# FMC_connector.net
KiCad netlist of a schematic drawn in Altium Designer
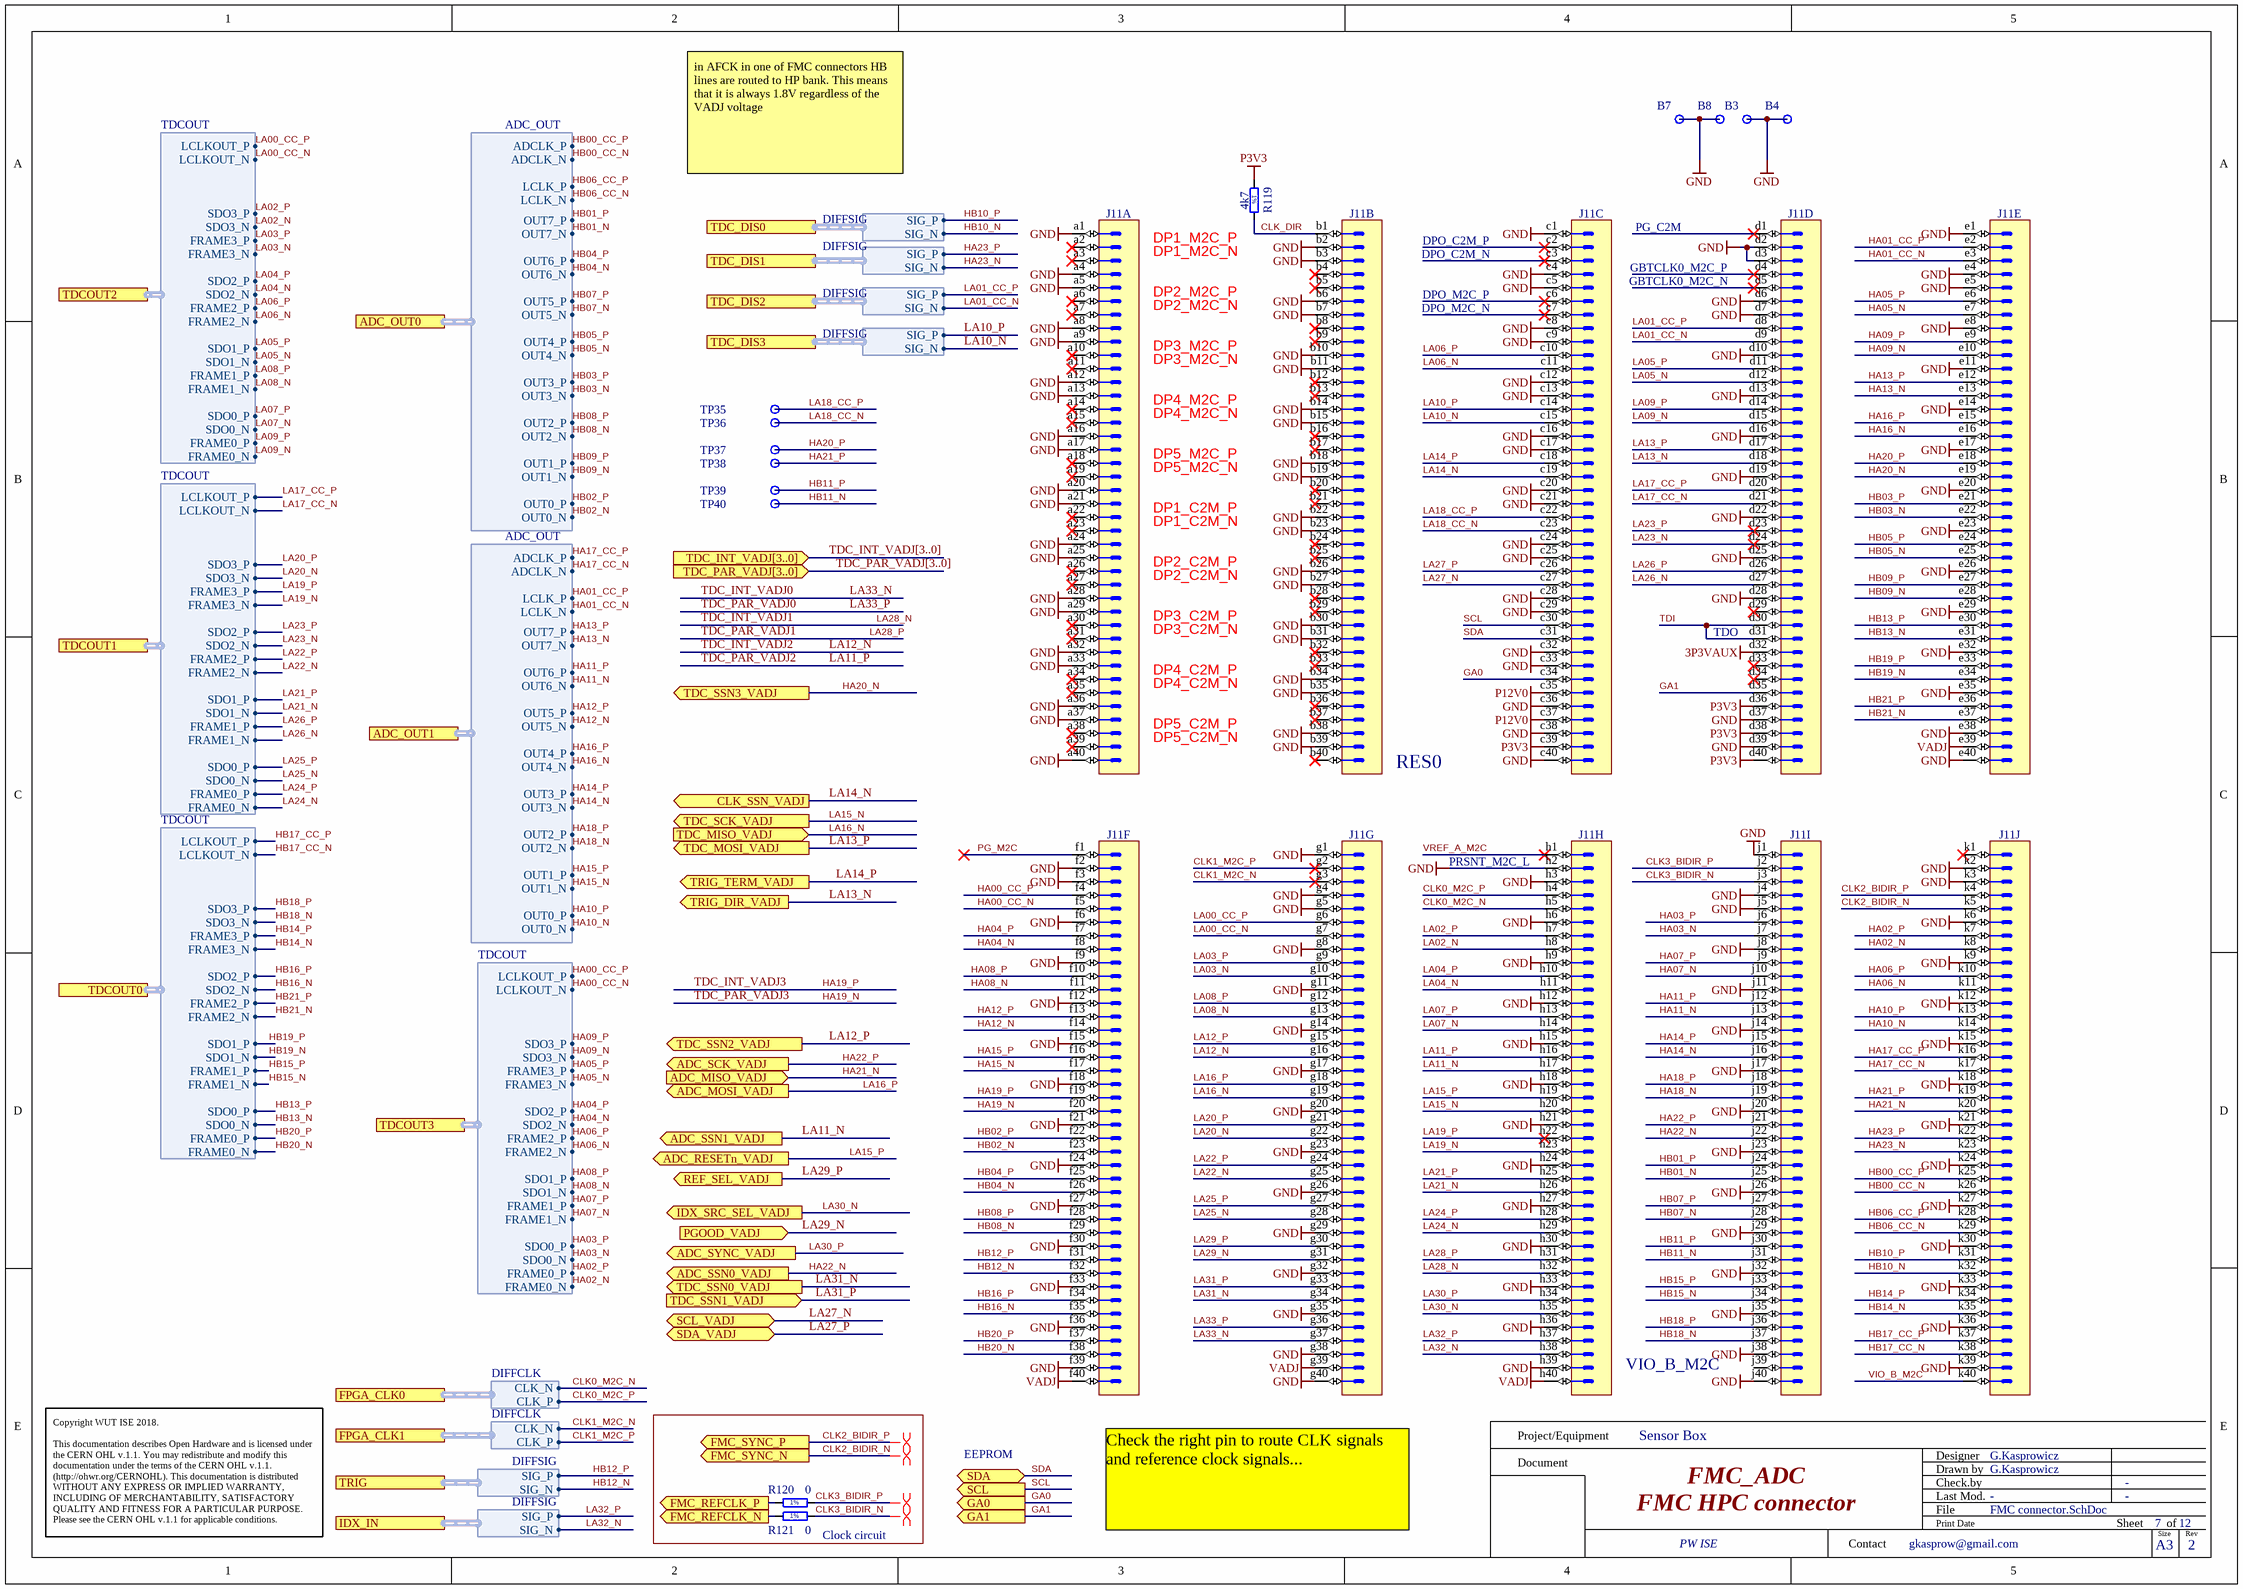
[diagram p0: FMC connector.SchDoc]

(export (version "E")
  (design (tool "Eeschema 10.0.6"))
  (components
    (comp (ref "B3")
      (value "Plated Hole")
      (footprint "MTG300_600")
      (description "Single Terminal Socket")
      (fields (field (name "PART NUMBER") "PLATED_HOLE3.0_PAD6.0") (field (name "AUTHOR") "CERN DEM JLC"))
      (libsource (lib "Eletro-mechanical") (part "Single Terminal Socket"))
    )
    (comp (ref "B4")
      (value "Plated Hole")
      (footprint "MTG300_600")
      (description "Single Terminal Socket")
      (fields (field (name "PART NUMBER") "PLATED_HOLE3.0_PAD6.0") (field (name "AUTHOR") "CERN DEM JLC"))
      (libsource (lib "Eletro-mechanical") (part "Single Terminal Socket"))
    )
    (comp (ref "B7")
      (value "Plated Hole")
      (footprint "MTG300_600")
      (description "Single Terminal Socket")
      (fields (field (name "PART NUMBER") "PLATED_HOLE3.0_PAD6.0") (field (name "AUTHOR") "CERN DEM JLC"))
      (libsource (lib "Eletro-mechanical") (part "Single Terminal Socket"))
    )
    (comp (ref "B8")
      (value "Plated Hole")
      (footprint "MTG300_600")
      (description "Single Terminal Socket")
      (fields (field (name "PART NUMBER") "PLATED_HOLE3.0_PAD6.0") (field (name "AUTHOR") "CERN DEM JLC"))
      (libsource (lib "Eletro-mechanical") (part "Single Terminal Socket"))
    )
    (comp (ref "J11")
      (value "VITA 57")
      (footprint "SAMTEC_ASP-134488-01")
      (description "Connector VITA 57, 400 Male contacts in 10 row abcdefghj")
      (fields
        (field (name "PART NUMBER") "SAMTEC_ASP-134488-01")
        (field (name "MANUFACTURER") "SAMTEC")
        (field (name "AUTHOR") "CERN DEM JLC")
      )
      (libsource (lib "Connectors") (part "Connector VITA 57 400 Male (abcdefghjk)"))
    )
    (comp (ref "R119")
      (value "4k7")
      (footprint "RESC1608X55N")
      (description "Resistor - 1%")
      (fields
        (field (name "PART NUMBER") "R0603_4K7_1%_0.1W_100PPM")
        (field (name "POWER") "0.1W")
        (field (name "AUTHOR") "CERN DEM JLC")
      )
      (libsource (lib "Resistors") (part "Resistor - 1%"))
    )
    (comp (ref "R120")
      (value "0")
      (footprint "RESC1005X40N")
      (description "Resistor - 1%")
      (fields
        (field (name "PART NUMBER") "R0402_0R_JUMPER")
        (field (name "MANUFACTURER") "GENERIC")
        (field (name "AUTHOR") "CERN DEM JLC")
      )
      (libsource (lib "Resistors") (part "Resistor - 1%"))
    )
    (comp (ref "R121")
      (value "0")
      (footprint "RESC1005X40N")
      (description "Resistor - 1%")
      (fields
        (field (name "PART NUMBER") "R0402_0R_JUMPER")
        (field (name "MANUFACTURER") "GENERIC")
        (field (name "AUTHOR") "CERN DEM JLC")
      )
      (libsource (lib "Resistors") (part "Resistor - 1%"))
    )
    (comp (ref "TP35")
      (value "Test Point")
      (footprint "TPS127")
      (fields (field (name "PART NUMBER") "SMD_PAD_1.27X1.27MM") (field (name "AUTHOR") "CERN DEM JLC"))
      (libsource (lib "Eletro-mechanical") (part "Test Point"))
    )
    (comp (ref "TP36")
      (value "Test Point")
      (footprint "TPS127")
      (fields (field (name "PART NUMBER") "SMD_PAD_1.27X1.27MM") (field (name "AUTHOR") "CERN DEM JLC"))
      (libsource (lib "Eletro-mechanical") (part "Test Point"))
    )
    (comp (ref "TP37")
      (value "Test Point")
      (footprint "TPS127")
      (fields (field (name "PART NUMBER") "SMD_PAD_1.27X1.27MM") (field (name "AUTHOR") "CERN DEM JLC"))
      (libsource (lib "Eletro-mechanical") (part "Test Point"))
    )
    (comp (ref "TP38")
      (value "Test Point")
      (footprint "TPS127")
      (fields (field (name "PART NUMBER") "SMD_PAD_1.27X1.27MM") (field (name "AUTHOR") "CERN DEM JLC"))
      (libsource (lib "Eletro-mechanical") (part "Test Point"))
    )
    (comp (ref "TP39")
      (value "Test Point")
      (footprint "TPS127")
      (fields (field (name "PART NUMBER") "SMD_PAD_1.27X1.27MM") (field (name "AUTHOR") "CERN DEM JLC"))
      (libsource (lib "Eletro-mechanical") (part "Test Point"))
    )
    (comp (ref "TP40")
      (value "Test Point")
      (footprint "TPS127")
      (fields (field (name "PART NUMBER") "SMD_PAD_1.27X1.27MM") (field (name "AUTHOR") "CERN DEM JLC"))
      (libsource (lib "Eletro-mechanical") (part "Test Point"))
    )
  )
  (nets
    (net (code "5") (name "/CLK0_M2C_N") (class "Default")
      (node (ref "J11") (pin "h5") (pinfunction "h5_h5") (pintype "bidirectional"))
    )
    (net (code "6") (name "/CLK0_M2C_P") (class "Default")
      (node (ref "J11") (pin "h4") (pinfunction "h4_h4") (pintype "bidirectional"))
    )
    (net (code "7") (name "/CLK1_M2C_N") (class "Default")
      (node (ref "J11") (pin "g3") (pinfunction "g3_g3") (pintype "bidirectional"))
    )
    (net (code "8") (name "/CLK1_M2C_P") (class "Default")
      (node (ref "J11") (pin "g2") (pinfunction "g2_g2") (pintype "bidirectional"))
    )
    (net (code "9") (name "/CLK2_BIDIR_N") (class "Default")
      (node (ref "J11") (pin "k5") (pinfunction "k5_k5") (pintype "bidirectional"))
    )
    (net (code "10") (name "/CLK2_BIDIR_P") (class "Default")
      (node (ref "J11") (pin "k4") (pinfunction "k4_k4") (pintype "bidirectional"))
    )
    (net (code "11") (name "/CLK3_BIDIR_N") (class "Default")
      (node (ref "J11") (pin "j3") (pinfunction "j3_j3") (pintype "bidirectional"))
      (node (ref "R121") (pin "2") (pinfunction "2_2") (pintype "passive"))
    )
    (net (code "12") (name "/CLK3_BIDIR_P") (class "Default")
      (node (ref "J11") (pin "j2") (pinfunction "j2_j2") (pintype "bidirectional"))
      (node (ref "R120") (pin "2") (pinfunction "2_2") (pintype "passive"))
    )
    (net (code "13") (name "/CLK_DIR") (class "Default")
      (node (ref "J11") (pin "b1") (pinfunction "b1_b1") (pintype "bidirectional"))
      (node (ref "R119") (pin "2") (pinfunction "2_2") (pintype "passive"))
    )
    (net (code "14") (name "/FMC_REFCLK_N") (class "Default")
      (node (ref "R121") (pin "1") (pinfunction "1_1") (pintype "passive"))
    )
    (net (code "15") (name "/FMC_REFCLK_P") (class "Default")
      (node (ref "R120") (pin "1") (pinfunction "1_1") (pintype "passive"))
    )
    (net (code "16") (name "/GA0") (class "Default")
      (node (ref "J11") (pin "c34") (pinfunction "c34_c34") (pintype "bidirectional"))
    )
    (net (code "17") (name "/GA1") (class "Default")
      (node (ref "J11") (pin "d35") (pinfunction "d35_d35") (pintype "bidirectional"))
    )
    (net (code "18") (name "/HA00_CC_N") (class "Default")
      (node (ref "J11") (pin "f5") (pinfunction "f5_f5") (pintype "bidirectional"))
    )
    (net (code "19") (name "/HA00_CC_P") (class "Default")
      (node (ref "J11") (pin "f4") (pinfunction "f4_f4") (pintype "bidirectional"))
    )
    (net (code "20") (name "/HA01_CC_N") (class "Default")
      (node (ref "J11") (pin "e3") (pinfunction "e3_e3") (pintype "bidirectional"))
    )
    (net (code "21") (name "/HA01_CC_P") (class "Default")
      (node (ref "J11") (pin "e2") (pinfunction "e2_e2") (pintype "bidirectional"))
    )
    (net (code "22") (name "/HA02_N") (class "Default")
      (node (ref "J11") (pin "k8") (pinfunction "k8_k8") (pintype "bidirectional"))
    )
    (net (code "23") (name "/HA02_P") (class "Default")
      (node (ref "J11") (pin "k7") (pinfunction "k7_k7") (pintype "bidirectional"))
    )
    (net (code "24") (name "/HA03_N") (class "Default")
      (node (ref "J11") (pin "j7") (pinfunction "j7_j7") (pintype "bidirectional"))
    )
    (net (code "25") (name "/HA03_P") (class "Default")
      (node (ref "J11") (pin "j6") (pinfunction "j6_j6") (pintype "bidirectional"))
    )
    (net (code "26") (name "/HA04_N") (class "Default")
      (node (ref "J11") (pin "f8") (pinfunction "f8_f8") (pintype "bidirectional"))
    )
    (net (code "27") (name "/HA04_P") (class "Default")
      (node (ref "J11") (pin "f7") (pinfunction "f7_f7") (pintype "bidirectional"))
    )
    (net (code "28") (name "/HA05_N") (class "Default")
      (node (ref "J11") (pin "e7") (pinfunction "e7_e7") (pintype "bidirectional"))
    )
    (net (code "29") (name "/HA05_P") (class "Default")
      (node (ref "J11") (pin "e6") (pinfunction "e6_e6") (pintype "bidirectional"))
    )
    (net (code "30") (name "/HA06_N") (class "Default")
      (node (ref "J11") (pin "k11") (pinfunction "k11_k11") (pintype "bidirectional"))
    )
    (net (code "31") (name "/HA06_P") (class "Default")
      (node (ref "J11") (pin "k10") (pinfunction "k10_k10") (pintype "bidirectional"))
    )
    (net (code "32") (name "/HA07_N") (class "Default")
      (node (ref "J11") (pin "j10") (pinfunction "j10_j10") (pintype "bidirectional"))
    )
    (net (code "33") (name "/HA07_P") (class "Default")
      (node (ref "J11") (pin "j9") (pinfunction "j9_j9") (pintype "bidirectional"))
    )
    (net (code "34") (name "/HA08_N") (class "Default")
      (node (ref "J11") (pin "f11") (pinfunction "f11_f11") (pintype "bidirectional"))
    )
    (net (code "35") (name "/HA08_P") (class "Default")
      (node (ref "J11") (pin "f10") (pinfunction "f10_f10") (pintype "bidirectional"))
    )
    (net (code "36") (name "/HA09_N") (class "Default")
      (node (ref "J11") (pin "e10") (pinfunction "e10_e10") (pintype "bidirectional"))
    )
    (net (code "37") (name "/HA09_P") (class "Default")
      (node (ref "J11") (pin "e9") (pinfunction "e9_e9") (pintype "bidirectional"))
    )
    (net (code "38") (name "/HA10_N") (class "Default")
      (node (ref "J11") (pin "k14") (pinfunction "k14_k14") (pintype "bidirectional"))
    )
    (net (code "39") (name "/HA10_P") (class "Default")
      (node (ref "J11") (pin "k13") (pinfunction "k13_k13") (pintype "bidirectional"))
    )
    (net (code "40") (name "/HA11_N") (class "Default")
      (node (ref "J11") (pin "j13") (pinfunction "j13_j13") (pintype "bidirectional"))
    )
    (net (code "41") (name "/HA11_P") (class "Default")
      (node (ref "J11") (pin "j12") (pinfunction "j12_j12") (pintype "bidirectional"))
    )
    (net (code "42") (name "/HA12_N") (class "Default")
      (node (ref "J11") (pin "f14") (pinfunction "f14_f14") (pintype "bidirectional"))
    )
    (net (code "43") (name "/HA12_P") (class "Default")
      (node (ref "J11") (pin "f13") (pinfunction "f13_f13") (pintype "bidirectional"))
    )
    (net (code "44") (name "/HA13_N") (class "Default")
      (node (ref "J11") (pin "e13") (pinfunction "e13_e13") (pintype "bidirectional"))
    )
    (net (code "45") (name "/HA13_P") (class "Default")
      (node (ref "J11") (pin "e12") (pinfunction "e12_e12") (pintype "bidirectional"))
    )
    (net (code "46") (name "/HA14_N") (class "Default")
      (node (ref "J11") (pin "j16") (pinfunction "j16_j16") (pintype "bidirectional"))
    )
    (net (code "47") (name "/HA14_P") (class "Default")
      (node (ref "J11") (pin "j15") (pinfunction "j15_j15") (pintype "bidirectional"))
    )
    (net (code "48") (name "/HA15_N") (class "Default")
      (node (ref "J11") (pin "f17") (pinfunction "f17_f17") (pintype "bidirectional"))
    )
    (net (code "49") (name "/HA15_P") (class "Default")
      (node (ref "J11") (pin "f16") (pinfunction "f16_f16") (pintype "bidirectional"))
    )
    (net (code "50") (name "/HA16_N") (class "Default")
      (node (ref "J11") (pin "e16") (pinfunction "e16_e16") (pintype "bidirectional"))
    )
    (net (code "51") (name "/HA16_P") (class "Default")
      (node (ref "J11") (pin "e15") (pinfunction "e15_e15") (pintype "bidirectional"))
    )
    (net (code "52") (name "/HA17_CC_N") (class "Default")
      (node (ref "J11") (pin "k17") (pinfunction "k17_k17") (pintype "bidirectional"))
    )
    (net (code "53") (name "/HA17_CC_P") (class "Default")
      (node (ref "J11") (pin "k16") (pinfunction "k16_k16") (pintype "bidirectional"))
    )
    (net (code "54") (name "/HA18_N") (class "Default")
      (node (ref "J11") (pin "j19") (pinfunction "j19_j19") (pintype "bidirectional"))
    )
    (net (code "55") (name "/HA18_P") (class "Default")
      (node (ref "J11") (pin "j18") (pinfunction "j18_j18") (pintype "bidirectional"))
    )
    (net (code "56") (name "/HA20_N") (class "Default")
      (node (ref "J11") (pin "e19") (pinfunction "e19_e19") (pintype "bidirectional"))
    )
    (net (code "57") (name "/HA20_P") (class "Default")
      (node (ref "J11") (pin "e18") (pinfunction "e18_e18") (pintype "bidirectional"))
      (node (ref "TP37") (pin "1") (pinfunction "1_1") (pintype "bidirectional"))
    )
    (net (code "58") (name "/HA21_N") (class "Default")
      (node (ref "J11") (pin "k20") (pinfunction "k20_k20") (pintype "bidirectional"))
    )
    (net (code "59") (name "/HA21_P") (class "Default")
      (node (ref "J11") (pin "k19") (pinfunction "k19_k19") (pintype "bidirectional"))
      (node (ref "TP38") (pin "1") (pinfunction "1_1") (pintype "bidirectional"))
    )
    (net (code "60") (name "/HA22_N") (class "Default")
      (node (ref "J11") (pin "j22") (pinfunction "j22_j22") (pintype "bidirectional"))
    )
    (net (code "61") (name "/HA22_P") (class "Default")
      (node (ref "J11") (pin "j21") (pinfunction "j21_j21") (pintype "bidirectional"))
    )
    (net (code "62") (name "/HA23_N") (class "Default")
      (node (ref "J11") (pin "k23") (pinfunction "k23_k23") (pintype "bidirectional"))
    )
    (net (code "63") (name "/HA23_P") (class "Default")
      (node (ref "J11") (pin "k22") (pinfunction "k22_k22") (pintype "bidirectional"))
    )
    (net (code "64") (name "/HB00_CC_N") (class "Default")
      (node (ref "J11") (pin "k26") (pinfunction "k26_k26") (pintype "bidirectional"))
    )
    (net (code "65") (name "/HB00_CC_P") (class "Default")
      (node (ref "J11") (pin "k25") (pinfunction "k25_k25") (pintype "bidirectional"))
    )
    (net (code "66") (name "/HB01_N") (class "Default")
      (node (ref "J11") (pin "j25") (pinfunction "j25_j25") (pintype "bidirectional"))
    )
    (net (code "67") (name "/HB01_P") (class "Default")
      (node (ref "J11") (pin "j24") (pinfunction "j24_j24") (pintype "bidirectional"))
    )
    (net (code "68") (name "/HB02_N") (class "Default")
      (node (ref "J11") (pin "f23") (pinfunction "f23_f23") (pintype "bidirectional"))
    )
    (net (code "69") (name "/HB02_P") (class "Default")
      (node (ref "J11") (pin "f22") (pinfunction "f22_f22") (pintype "bidirectional"))
    )
    (net (code "70") (name "/HB03_N") (class "Default")
      (node (ref "J11") (pin "e22") (pinfunction "e22_e22") (pintype "bidirectional"))
    )
    (net (code "71") (name "/HB03_P") (class "Default")
      (node (ref "J11") (pin "e21") (pinfunction "e21_e21") (pintype "bidirectional"))
    )
    (net (code "72") (name "/HB04_N") (class "Default")
      (node (ref "J11") (pin "f26") (pinfunction "f26_f26") (pintype "bidirectional"))
    )
    (net (code "73") (name "/HB04_P") (class "Default")
      (node (ref "J11") (pin "f25") (pinfunction "f25_f25") (pintype "bidirectional"))
    )
    (net (code "74") (name "/HB05_N") (class "Default")
      (node (ref "J11") (pin "e25") (pinfunction "e25_e25") (pintype "bidirectional"))
    )
    (net (code "75") (name "/HB05_P") (class "Default")
      (node (ref "J11") (pin "e24") (pinfunction "e24_e24") (pintype "bidirectional"))
    )
    (net (code "76") (name "/HB06_CC_N") (class "Default")
      (node (ref "J11") (pin "k29") (pinfunction "k29_k29") (pintype "bidirectional"))
    )
    (net (code "77") (name "/HB06_CC_P") (class "Default")
      (node (ref "J11") (pin "k28") (pinfunction "k28_k28") (pintype "bidirectional"))
    )
    (net (code "78") (name "/HB07_N") (class "Default")
      (node (ref "J11") (pin "j28") (pinfunction "j28_j28") (pintype "bidirectional"))
    )
    (net (code "79") (name "/HB07_P") (class "Default")
      (node (ref "J11") (pin "j27") (pinfunction "j27_j27") (pintype "bidirectional"))
    )
    (net (code "80") (name "/HB08_N") (class "Default")
      (node (ref "J11") (pin "f29") (pinfunction "f29_f29") (pintype "bidirectional"))
    )
    (net (code "81") (name "/HB08_P") (class "Default")
      (node (ref "J11") (pin "f28") (pinfunction "f28_f28") (pintype "bidirectional"))
    )
    (net (code "82") (name "/HB09_N") (class "Default")
      (node (ref "J11") (pin "e28") (pinfunction "e28_e28") (pintype "bidirectional"))
    )
    (net (code "83") (name "/HB09_P") (class "Default")
      (node (ref "J11") (pin "e27") (pinfunction "e27_e27") (pintype "bidirectional"))
    )
    (net (code "84") (name "/HB10_N") (class "Default")
      (node (ref "J11") (pin "k32") (pinfunction "k32_k32") (pintype "bidirectional"))
    )
    (net (code "85") (name "/HB10_P") (class "Default")
      (node (ref "J11") (pin "k31") (pinfunction "k31_k31") (pintype "bidirectional"))
    )
    (net (code "86") (name "/HB11_N") (class "Default")
      (node (ref "J11") (pin "j31") (pinfunction "j31_j31") (pintype "bidirectional"))
      (node (ref "TP40") (pin "1") (pinfunction "1_1") (pintype "bidirectional"))
    )
    (net (code "87") (name "/HB11_P") (class "Default")
      (node (ref "J11") (pin "j30") (pinfunction "j30_j30") (pintype "bidirectional"))
      (node (ref "TP39") (pin "1") (pinfunction "1_1") (pintype "bidirectional"))
    )
    (net (code "88") (name "/HB12_N") (class "Default")
      (node (ref "J11") (pin "f32") (pinfunction "f32_f32") (pintype "bidirectional"))
    )
    (net (code "89") (name "/HB12_P") (class "Default")
      (node (ref "J11") (pin "f31") (pinfunction "f31_f31") (pintype "bidirectional"))
    )
    (net (code "90") (name "/HB13_N") (class "Default")
      (node (ref "J11") (pin "e31") (pinfunction "e31_e31") (pintype "bidirectional"))
    )
    (net (code "91") (name "/HB13_P") (class "Default")
      (node (ref "J11") (pin "e30") (pinfunction "e30_e30") (pintype "bidirectional"))
    )
    (net (code "92") (name "/HB14_N") (class "Default")
      (node (ref "J11") (pin "k35") (pinfunction "k35_k35") (pintype "bidirectional"))
    )
    (net (code "93") (name "/HB14_P") (class "Default")
      (node (ref "J11") (pin "k34") (pinfunction "k34_k34") (pintype "bidirectional"))
    )
    (net (code "94") (name "/HB15_N") (class "Default")
      (node (ref "J11") (pin "j34") (pinfunction "j34_j34") (pintype "bidirectional"))
    )
    (net (code "95") (name "/HB15_P") (class "Default")
      (node (ref "J11") (pin "j33") (pinfunction "j33_j33") (pintype "bidirectional"))
    )
    (net (code "96") (name "/HB16_N") (class "Default")
      (node (ref "J11") (pin "f35") (pinfunction "f35_f35") (pintype "bidirectional"))
    )
    (net (code "97") (name "/HB16_P") (class "Default")
      (node (ref "J11") (pin "f34") (pinfunction "f34_f34") (pintype "bidirectional"))
    )
    (net (code "98") (name "/HB17_CC_N") (class "Default")
      (node (ref "J11") (pin "k38") (pinfunction "k38_k38") (pintype "bidirectional"))
    )
    (net (code "99") (name "/HB17_CC_P") (class "Default")
      (node (ref "J11") (pin "k37") (pinfunction "k37_k37") (pintype "bidirectional"))
    )
    (net (code "100") (name "/HB18_N") (class "Default")
      (node (ref "J11") (pin "j37") (pinfunction "j37_j37") (pintype "bidirectional"))
    )
    (net (code "101") (name "/HB18_P") (class "Default")
      (node (ref "J11") (pin "j36") (pinfunction "j36_j36") (pintype "bidirectional"))
    )
    (net (code "102") (name "/HB19_N") (class "Default")
      (node (ref "J11") (pin "e34") (pinfunction "e34_e34") (pintype "bidirectional"))
    )
    (net (code "103") (name "/HB19_P") (class "Default")
      (node (ref "J11") (pin "e33") (pinfunction "e33_e33") (pintype "bidirectional"))
    )
    (net (code "104") (name "/HB20_N") (class "Default")
      (node (ref "J11") (pin "f38") (pinfunction "f38_f38") (pintype "bidirectional"))
    )
    (net (code "105") (name "/HB20_P") (class "Default")
      (node (ref "J11") (pin "f37") (pinfunction "f37_f37") (pintype "bidirectional"))
    )
    (net (code "106") (name "/HB21_N") (class "Default")
      (node (ref "J11") (pin "e37") (pinfunction "e37_e37") (pintype "bidirectional"))
    )
    (net (code "107") (name "/HB21_P") (class "Default")
      (node (ref "J11") (pin "e36") (pinfunction "e36_e36") (pintype "bidirectional"))
    )
    (net (code "108") (name "/LA00_CC_N") (class "Default")
      (node (ref "J11") (pin "g7") (pinfunction "g7_g7") (pintype "bidirectional"))
    )
    (net (code "109") (name "/LA00_CC_P") (class "Default")
      (node (ref "J11") (pin "g6") (pinfunction "g6_g6") (pintype "bidirectional"))
    )
    (net (code "110") (name "/LA01_CC_N") (class "Default")
      (node (ref "J11") (pin "d9") (pinfunction "d9_d9") (pintype "bidirectional"))
    )
    (net (code "111") (name "/LA01_CC_P") (class "Default")
      (node (ref "J11") (pin "d8") (pinfunction "d8_d8") (pintype "bidirectional"))
    )
    (net (code "112") (name "/LA02_N") (class "Default")
      (node (ref "J11") (pin "h8") (pinfunction "h8_h8") (pintype "bidirectional"))
    )
    (net (code "113") (name "/LA02_P") (class "Default")
      (node (ref "J11") (pin "h7") (pinfunction "h7_h7") (pintype "bidirectional"))
    )
    (net (code "114") (name "/LA03_N") (class "Default")
      (node (ref "J11") (pin "g10") (pinfunction "g10_g10") (pintype "bidirectional"))
    )
    (net (code "115") (name "/LA03_P") (class "Default")
      (node (ref "J11") (pin "g9") (pinfunction "g9_g9") (pintype "bidirectional"))
    )
    (net (code "116") (name "/LA04_N") (class "Default")
      (node (ref "J11") (pin "h11") (pinfunction "h11_h11") (pintype "bidirectional"))
    )
    (net (code "117") (name "/LA04_P") (class "Default")
      (node (ref "J11") (pin "h10") (pinfunction "h10_h10") (pintype "bidirectional"))
    )
    (net (code "118") (name "/LA05_N") (class "Default")
      (node (ref "J11") (pin "d12") (pinfunction "d12_d12") (pintype "bidirectional"))
    )
    (net (code "119") (name "/LA05_P") (class "Default")
      (node (ref "J11") (pin "d11") (pinfunction "d11_d11") (pintype "bidirectional"))
    )
    (net (code "120") (name "/LA06_N") (class "Default")
      (node (ref "J11") (pin "c11") (pinfunction "c11_c11") (pintype "bidirectional"))
    )
    (net (code "121") (name "/LA06_P") (class "Default")
      (node (ref "J11") (pin "c10") (pinfunction "c10_c10") (pintype "bidirectional"))
    )
    (net (code "122") (name "/LA07_N") (class "Default")
      (node (ref "J11") (pin "h14") (pinfunction "h14_h14") (pintype "bidirectional"))
    )
    (net (code "123") (name "/LA07_P") (class "Default")
      (node (ref "J11") (pin "h13") (pinfunction "h13_h13") (pintype "bidirectional"))
    )
    (net (code "124") (name "/LA08_N") (class "Default")
      (node (ref "J11") (pin "g13") (pinfunction "g13_g13") (pintype "bidirectional"))
    )
    (net (code "125") (name "/LA08_P") (class "Default")
      (node (ref "J11") (pin "g12") (pinfunction "g12_g12") (pintype "bidirectional"))
    )
    (net (code "126") (name "/LA09_N") (class "Default")
      (node (ref "J11") (pin "d15") (pinfunction "d15_d15") (pintype "bidirectional"))
    )
    (net (code "127") (name "/LA09_P") (class "Default")
      (node (ref "J11") (pin "d14") (pinfunction "d14_d14") (pintype "bidirectional"))
    )
    (net (code "128") (name "/LA10_N") (class "Default")
      (node (ref "J11") (pin "c15") (pinfunction "c15_c15") (pintype "bidirectional"))
    )
    (net (code "129") (name "/LA10_P") (class "Default")
      (node (ref "J11") (pin "c14") (pinfunction "c14_c14") (pintype "bidirectional"))
    )
    (net (code "130") (name "/LA11_N") (class "Default")
      (node (ref "J11") (pin "h17") (pinfunction "h17_h17") (pintype "bidirectional"))
    )
    (net (code "131") (name "/LA12_P") (class "Default")
      (node (ref "J11") (pin "g15") (pinfunction "g15_g15") (pintype "bidirectional"))
    )
    (net (code "132") (name "/LA13_N") (class "Default")
      (node (ref "J11") (pin "d18") (pinfunction "d18_d18") (pintype "bidirectional"))
    )
    (net (code "133") (name "/LA13_P") (class "Default")
      (node (ref "J11") (pin "d17") (pinfunction "d17_d17") (pintype "bidirectional"))
    )
    (net (code "134") (name "/LA14_N") (class "Default")
      (node (ref "J11") (pin "c19") (pinfunction "c19_c19") (pintype "bidirectional"))
    )
    (net (code "135") (name "/LA14_P") (class "Default")
      (node (ref "J11") (pin "c18") (pinfunction "c18_c18") (pintype "bidirectional"))
    )
    (net (code "136") (name "/LA15_N") (class "Default")
      (node (ref "J11") (pin "h20") (pinfunction "h20_h20") (pintype "bidirectional"))
    )
    (net (code "137") (name "/LA15_P") (class "Default")
      (node (ref "J11") (pin "h19") (pinfunction "h19_h19") (pintype "bidirectional"))
    )
    (net (code "138") (name "/LA16_N") (class "Default")
      (node (ref "J11") (pin "g19") (pinfunction "g19_g19") (pintype "bidirectional"))
    )
    (net (code "139") (name "/LA16_P") (class "Default")
      (node (ref "J11") (pin "g18") (pinfunction "g18_g18") (pintype "bidirectional"))
    )
    (net (code "140") (name "/LA17_CC_N") (class "Default")
      (node (ref "J11") (pin "d21") (pinfunction "d21_d21") (pintype "bidirectional"))
    )
    (net (code "141") (name "/LA17_CC_P") (class "Default")
      (node (ref "J11") (pin "d20") (pinfunction "d20_d20") (pintype "bidirectional"))
    )
    (net (code "142") (name "/LA18_CC_N") (class "Default")
      (node (ref "J11") (pin "c23") (pinfunction "c23_c23") (pintype "bidirectional"))
      (node (ref "TP36") (pin "1") (pinfunction "1_1") (pintype "bidirectional"))
    )
    (net (code "143") (name "/LA18_CC_P") (class "Default")
      (node (ref "J11") (pin "c22") (pinfunction "c22_c22") (pintype "bidirectional"))
      (node (ref "TP35") (pin "1") (pinfunction "1_1") (pintype "bidirectional"))
    )
    (net (code "144") (name "/LA19_N") (class "Default")
      (node (ref "J11") (pin "h23") (pinfunction "h23_h23") (pintype "bidirectional"))
    )
    (net (code "145") (name "/LA19_P") (class "Default")
      (node (ref "J11") (pin "h22") (pinfunction "h22_h22") (pintype "bidirectional+no_connect"))
    )
    (net (code "146") (name "/LA20_N") (class "Default")
      (node (ref "J11") (pin "g22") (pinfunction "g22_g22") (pintype "bidirectional"))
    )
    (net (code "147") (name "/LA20_P") (class "Default")
      (node (ref "J11") (pin "g21") (pinfunction "g21_g21") (pintype "bidirectional"))
    )
    (net (code "148") (name "/LA21_N") (class "Default")
      (node (ref "J11") (pin "h26") (pinfunction "h26_h26") (pintype "bidirectional"))
    )
    (net (code "149") (name "/LA21_P") (class "Default")
      (node (ref "J11") (pin "h25") (pinfunction "h25_h25") (pintype "bidirectional"))
    )
    (net (code "150") (name "/LA22_N") (class "Default")
      (node (ref "J11") (pin "g25") (pinfunction "g25_g25") (pintype "bidirectional"))
    )
    (net (code "151") (name "/LA22_P") (class "Default")
      (node (ref "J11") (pin "g24") (pinfunction "g24_g24") (pintype "bidirectional"))
    )
    (net (code "152") (name "/LA23_N") (class "Default")
      (node (ref "J11") (pin "d24") (pinfunction "d24_d24") (pintype "bidirectional+no_connect"))
    )
    (net (code "153") (name "/LA23_P") (class "Default")
      (node (ref "J11") (pin "d23") (pinfunction "d23_d23") (pintype "bidirectional+no_connect"))
    )
    (net (code "154") (name "/LA24_N") (class "Default")
      (node (ref "J11") (pin "h29") (pinfunction "h29_h29") (pintype "bidirectional"))
    )
    (net (code "155") (name "/LA24_P") (class "Default")
      (node (ref "J11") (pin "h28") (pinfunction "h28_h28") (pintype "bidirectional"))
    )
    (net (code "156") (name "/LA25_N") (class "Default")
      (node (ref "J11") (pin "g28") (pinfunction "g28_g28") (pintype "bidirectional"))
    )
    (net (code "157") (name "/LA25_P") (class "Default")
      (node (ref "J11") (pin "g27") (pinfunction "g27_g27") (pintype "bidirectional"))
    )
    (net (code "158") (name "/LA26_N") (class "Default")
      (node (ref "J11") (pin "d27") (pinfunction "d27_d27") (pintype "bidirectional"))
    )
    (net (code "159") (name "/LA26_P") (class "Default")
      (node (ref "J11") (pin "d26") (pinfunction "d26_d26") (pintype "bidirectional"))
    )
    (net (code "160") (name "/LA27_N") (class "Default")
      (node (ref "J11") (pin "c27") (pinfunction "c27_c27") (pintype "bidirectional"))
    )
    (net (code "161") (name "/LA27_P") (class "Default")
      (node (ref "J11") (pin "c26") (pinfunction "c26_c26") (pintype "bidirectional"))
    )
    (net (code "162") (name "/LA29_N") (class "Default")
      (node (ref "J11") (pin "g31") (pinfunction "g31_g31") (pintype "bidirectional"))
    )
    (net (code "163") (name "/LA29_P") (class "Default")
      (node (ref "J11") (pin "g30") (pinfunction "g30_g30") (pintype "bidirectional"))
    )
    (net (code "164") (name "/LA30_N") (class "Default")
      (node (ref "J11") (pin "h35") (pinfunction "h35_h35") (pintype "bidirectional"))
    )
    (net (code "165") (name "/LA30_P") (class "Default")
      (node (ref "J11") (pin "h34") (pinfunction "h34_h34") (pintype "bidirectional"))
    )
    (net (code "166") (name "/LA31_N") (class "Default")
      (node (ref "J11") (pin "g34") (pinfunction "g34_g34") (pintype "bidirectional"))
    )
    (net (code "167") (name "/LA31_P") (class "Default")
      (node (ref "J11") (pin "g33") (pinfunction "g33_g33") (pintype "bidirectional"))
    )
    (net (code "168") (name "/LA32_N") (class "Default")
      (node (ref "J11") (pin "h38") (pinfunction "h38_h38") (pintype "bidirectional"))
    )
    (net (code "169") (name "/LA32_P") (class "Default")
      (node (ref "J11") (pin "h37") (pinfunction "h37_h37") (pintype "bidirectional"))
    )
    (net (code "170") (name "/PG_M2C") (class "Default")
      (node (ref "J11") (pin "f1") (pinfunction "f1_f1") (pintype "bidirectional+no_connect"))
    )
    (net (code "171") (name "/SCL") (class "Default")
      (node (ref "J11") (pin "c30") (pinfunction "c30_c30") (pintype "bidirectional"))
    )
    (net (code "172") (name "/SDA") (class "Default")
      (node (ref "J11") (pin "c31") (pinfunction "c31_c31") (pintype "bidirectional"))
    )
    (net (code "173") (name "/TDC_INT_VADJ0") (class "Default")
      (node (ref "J11") (pin "g37") (pinfunction "g37_g37") (pintype "bidirectional"))
    )
    (net (code "174") (name "/TDC_INT_VADJ1") (class "Default")
      (node (ref "J11") (pin "h32") (pinfunction "h32_h32") (pintype "bidirectional"))
    )
    (net (code "175") (name "/TDC_INT_VADJ2") (class "Default")
      (node (ref "J11") (pin "g16") (pinfunction "g16_g16") (pintype "bidirectional"))
    )
    (net (code "176") (name "/TDC_INT_VADJ3") (class "Default")
      (node (ref "J11") (pin "f19") (pinfunction "f19_f19") (pintype "bidirectional"))
    )
    (net (code "178") (name "/TDC_PAR_VADJ0") (class "Default")
      (node (ref "J11") (pin "g36") (pinfunction "g36_g36") (pintype "bidirectional"))
    )
    (net (code "179") (name "/TDC_PAR_VADJ1") (class "Default")
      (node (ref "J11") (pin "h31") (pinfunction "h31_h31") (pintype "bidirectional"))
    )
    (net (code "180") (name "/TDC_PAR_VADJ2") (class "Default")
      (node (ref "J11") (pin "h16") (pinfunction "h16_h16") (pintype "bidirectional"))
    )
    (net (code "181") (name "/TDC_PAR_VADJ3") (class "Default")
      (node (ref "J11") (pin "f20") (pinfunction "f20_f20") (pintype "bidirectional"))
    )
    (net (code "183") (name "/TDI") (class "Default")
      (node (ref "J11") (pin "d30") (pinfunction "d30_d30") (pintype "bidirectional"))
      (node (ref "J11") (pin "d31") (pinfunction "d31_d31") (pintype "bidirectional"))
    )
    (net (code "184") (name "/VIO_B_M2C") (class "Default")
      (node (ref "J11") (pin "k40") (pinfunction "k40_k40") (pintype "bidirectional"))
    )
    (net (code "185") (name "/VREF_A_M2C") (class "Default")
      (node (ref "J11") (pin "h1") (pinfunction "h1_h1") (pintype "bidirectional+no_connect"))
    )
    (net (code "190") (name "3P3VAUX") (class "Default")
      (node (ref "J11") (pin "d32") (pinfunction "d32_d32") (pintype "bidirectional"))
    )
    (net (code "191") (name "GND") (class "Default")
      (node (ref "B3") (pin "1") (pinfunction "1_1") (pintype "bidirectional"))
      (node (ref "B4") (pin "1") (pinfunction "1_1") (pintype "bidirectional"))
      (node (ref "B7") (pin "1") (pinfunction "1_1") (pintype "bidirectional"))
      (node (ref "B8") (pin "1") (pinfunction "1_1") (pintype "bidirectional"))
      (node (ref "J11") (pin "a1") (pinfunction "a1_a1") (pintype "bidirectional"))
      (node (ref "J11") (pin "a12") (pinfunction "a12_a12") (pintype "bidirectional"))
      (node (ref "J11") (pin "a13") (pinfunction "a13_a13") (pintype "bidirectional"))
      (node (ref "J11") (pin "a16") (pinfunction "a16_a16") (pintype "bidirectional"))
      (node (ref "J11") (pin "a17") (pinfunction "a17_a17") (pintype "bidirectional"))
      (node (ref "J11") (pin "a20") (pinfunction "a20_a20") (pintype "bidirectional"))
      (node (ref "J11") (pin "a21") (pinfunction "a21_a21") (pintype "bidirectional"))
      (node (ref "J11") (pin "a24") (pinfunction "a24_a24") (pintype "bidirectional"))
      (node (ref "J11") (pin "a25") (pinfunction "a25_a25") (pintype "bidirectional"))
      (node (ref "J11") (pin "a28") (pinfunction "a28_a28") (pintype "bidirectional"))
      (node (ref "J11") (pin "a29") (pinfunction "a29_a29") (pintype "bidirectional"))
      (node (ref "J11") (pin "a32") (pinfunction "a32_a32") (pintype "bidirectional"))
      (node (ref "J11") (pin "a33") (pinfunction "a33_a33") (pintype "bidirectional"))
      (node (ref "J11") (pin "a36") (pinfunction "a36_a36") (pintype "bidirectional"))
      (node (ref "J11") (pin "a37") (pinfunction "a37_a37") (pintype "bidirectional"))
      (node (ref "J11") (pin "a4") (pinfunction "a4_a4") (pintype "bidirectional"))
      (node (ref "J11") (pin "a40") (pinfunction "a40_a40") (pintype "bidirectional"))
      (node (ref "J11") (pin "a5") (pinfunction "a5_a5") (pintype "bidirectional"))
      (node (ref "J11") (pin "a8") (pinfunction "a8_a8") (pintype "bidirectional"))
      (node (ref "J11") (pin "a9") (pinfunction "a9_a9") (pintype "bidirectional"))
      (node (ref "J11") (pin "b10") (pinfunction "b10_b10") (pintype "bidirectional"))
      (node (ref "J11") (pin "b11") (pinfunction "b11_b11") (pintype "bidirectional"))
      (node (ref "J11") (pin "b14") (pinfunction "b14_b14") (pintype "bidirectional"))
      (node (ref "J11") (pin "b15") (pinfunction "b15_b15") (pintype "bidirectional"))
      (node (ref "J11") (pin "b18") (pinfunction "b18_b18") (pintype "bidirectional"))
      (node (ref "J11") (pin "b19") (pinfunction "b19_b19") (pintype "bidirectional"))
      (node (ref "J11") (pin "b2") (pinfunction "b2_b2") (pintype "bidirectional"))
      (node (ref "J11") (pin "b22") (pinfunction "b22_b22") (pintype "bidirectional"))
      (node (ref "J11") (pin "b23") (pinfunction "b23_b23") (pintype "bidirectional"))
      (node (ref "J11") (pin "b26") (pinfunction "b26_b26") (pintype "bidirectional"))
      (node (ref "J11") (pin "b27") (pinfunction "b27_b27") (pintype "bidirectional"))
      (node (ref "J11") (pin "b3") (pinfunction "b3_b3") (pintype "bidirectional"))
      (node (ref "J11") (pin "b30") (pinfunction "b30_b30") (pintype "bidirectional"))
      (node (ref "J11") (pin "b31") (pinfunction "b31_b31") (pintype "bidirectional"))
      (node (ref "J11") (pin "b34") (pinfunction "b34_b34") (pintype "bidirectional"))
      (node (ref "J11") (pin "b35") (pinfunction "b35_b35") (pintype "bidirectional"))
      (node (ref "J11") (pin "b38") (pinfunction "b38_b38") (pintype "bidirectional"))
      (node (ref "J11") (pin "b39") (pinfunction "b39_b39") (pintype "bidirectional"))
      (node (ref "J11") (pin "b6") (pinfunction "b6_b6") (pintype "bidirectional"))
      (node (ref "J11") (pin "b7") (pinfunction "b7_b7") (pintype "bidirectional"))
      (node (ref "J11") (pin "c1") (pinfunction "c1_c1") (pintype "bidirectional"))
      (node (ref "J11") (pin "c12") (pinfunction "c12_c12") (pintype "bidirectional"))
      (node (ref "J11") (pin "c13") (pinfunction "c13_c13") (pintype "bidirectional"))
      (node (ref "J11") (pin "c16") (pinfunction "c16_c16") (pintype "bidirectional"))
      (node (ref "J11") (pin "c17") (pinfunction "c17_c17") (pintype "bidirectional"))
      (node (ref "J11") (pin "c20") (pinfunction "c20_c20") (pintype "bidirectional"))
      (node (ref "J11") (pin "c21") (pinfunction "c21_c21") (pintype "bidirectional"))
      (node (ref "J11") (pin "c24") (pinfunction "c24_c24") (pintype "bidirectional"))
      (node (ref "J11") (pin "c25") (pinfunction "c25_c25") (pintype "bidirectional"))
      (node (ref "J11") (pin "c28") (pinfunction "c28_c28") (pintype "bidirectional"))
      (node (ref "J11") (pin "c29") (pinfunction "c29_c29") (pintype "bidirectional"))
      (node (ref "J11") (pin "c32") (pinfunction "c32_c32") (pintype "bidirectional"))
      (node (ref "J11") (pin "c33") (pinfunction "c33_c33") (pintype "bidirectional"))
      (node (ref "J11") (pin "c36") (pinfunction "c36_c36") (pintype "bidirectional"))
      (node (ref "J11") (pin "c38") (pinfunction "c38_c38") (pintype "bidirectional"))
      (node (ref "J11") (pin "c4") (pinfunction "c4_c4") (pintype "bidirectional"))
      (node (ref "J11") (pin "c40") (pinfunction "c40_c40") (pintype "bidirectional"))
      (node (ref "J11") (pin "c5") (pinfunction "c5_c5") (pintype "bidirectional"))
      (node (ref "J11") (pin "c8") (pinfunction "c8_c8") (pintype "bidirectional"))
      (node (ref "J11") (pin "c9") (pinfunction "c9_c9") (pintype "bidirectional"))
      (node (ref "J11") (pin "d10") (pinfunction "d10_d10") (pintype "bidirectional"))
      (node (ref "J11") (pin "d13") (pinfunction "d13_d13") (pintype "bidirectional"))
      (node (ref "J11") (pin "d16") (pinfunction "d16_d16") (pintype "bidirectional"))
      (node (ref "J11") (pin "d19") (pinfunction "d19_d19") (pintype "bidirectional"))
      (node (ref "J11") (pin "d2") (pinfunction "d2_d2") (pintype "bidirectional"))
      (node (ref "J11") (pin "d22") (pinfunction "d22_d22") (pintype "bidirectional"))
      (node (ref "J11") (pin "d25") (pinfunction "d25_d25") (pintype "bidirectional"))
      (node (ref "J11") (pin "d28") (pinfunction "d28_d28") (pintype "bidirectional"))
      (node (ref "J11") (pin "d3") (pinfunction "d3_d3") (pintype "bidirectional"))
      (node (ref "J11") (pin "d37") (pinfunction "d37_d37") (pintype "bidirectional"))
      (node (ref "J11") (pin "d39") (pinfunction "d39_d39") (pintype "bidirectional"))
      (node (ref "J11") (pin "d6") (pinfunction "d6_d6") (pintype "bidirectional"))
      (node (ref "J11") (pin "d7") (pinfunction "d7_d7") (pintype "bidirectional"))
      (node (ref "J11") (pin "e1") (pinfunction "e1_e1") (pintype "bidirectional"))
      (node (ref "J11") (pin "e11") (pinfunction "e11_e11") (pintype "bidirectional"))
      (node (ref "J11") (pin "e14") (pinfunction "e14_e14") (pintype "bidirectional"))
      (node (ref "J11") (pin "e17") (pinfunction "e17_e17") (pintype "bidirectional"))
      (node (ref "J11") (pin "e20") (pinfunction "e20_e20") (pintype "bidirectional"))
      (node (ref "J11") (pin "e23") (pinfunction "e23_e23") (pintype "bidirectional"))
      (node (ref "J11") (pin "e26") (pinfunction "e26_e26") (pintype "bidirectional"))
      (node (ref "J11") (pin "e29") (pinfunction "e29_e29") (pintype "bidirectional"))
      (node (ref "J11") (pin "e32") (pinfunction "e32_e32") (pintype "bidirectional"))
      (node (ref "J11") (pin "e35") (pinfunction "e35_e35") (pintype "bidirectional"))
      (node (ref "J11") (pin "e38") (pinfunction "e38_e38") (pintype "bidirectional"))
      (node (ref "J11") (pin "e4") (pinfunction "e4_e4") (pintype "bidirectional"))
      (node (ref "J11") (pin "e40") (pinfunction "e40_e40") (pintype "bidirectional"))
      (node (ref "J11") (pin "e5") (pinfunction "e5_e5") (pintype "bidirectional"))
      (node (ref "J11") (pin "e8") (pinfunction "e8_e8") (pintype "bidirectional"))
      (node (ref "J11") (pin "f12") (pinfunction "f12_f12") (pintype "bidirectional"))
      (node (ref "J11") (pin "f15") (pinfunction "f15_f15") (pintype "bidirectional"))
      (node (ref "J11") (pin "f18") (pinfunction "f18_f18") (pintype "bidirectional"))
      (node (ref "J11") (pin "f2") (pinfunction "f2_f2") (pintype "bidirectional"))
      (node (ref "J11") (pin "f21") (pinfunction "f21_f21") (pintype "bidirectional"))
      (node (ref "J11") (pin "f24") (pinfunction "f24_f24") (pintype "bidirectional"))
      (node (ref "J11") (pin "f27") (pinfunction "f27_f27") (pintype "bidirectional"))
      (node (ref "J11") (pin "f3") (pinfunction "f3_f3") (pintype "bidirectional"))
      (node (ref "J11") (pin "f30") (pinfunction "f30_f30") (pintype "bidirectional"))
      (node (ref "J11") (pin "f33") (pinfunction "f33_f33") (pintype "bidirectional"))
      (node (ref "J11") (pin "f36") (pinfunction "f36_f36") (pintype "bidirectional"))
      (node (ref "J11") (pin "f39") (pinfunction "f39_f39") (pintype "bidirectional"))
      (node (ref "J11") (pin "f6") (pinfunction "f6_f6") (pintype "bidirectional"))
      (node (ref "J11") (pin "f9") (pinfunction "f9_f9") (pintype "bidirectional"))
      (node (ref "J11") (pin "g1") (pinfunction "g1_g1") (pintype "bidirectional"))
      (node (ref "J11") (pin "g11") (pinfunction "g11_g11") (pintype "bidirectional"))
      (node (ref "J11") (pin "g14") (pinfunction "g14_g14") (pintype "bidirectional"))
      (node (ref "J11") (pin "g17") (pinfunction "g17_g17") (pintype "bidirectional"))
      (node (ref "J11") (pin "g20") (pinfunction "g20_g20") (pintype "bidirectional"))
      (node (ref "J11") (pin "g23") (pinfunction "g23_g23") (pintype "bidirectional"))
      (node (ref "J11") (pin "g26") (pinfunction "g26_g26") (pintype "bidirectional"))
      (node (ref "J11") (pin "g29") (pinfunction "g29_g29") (pintype "bidirectional"))
      (node (ref "J11") (pin "g32") (pinfunction "g32_g32") (pintype "bidirectional"))
      (node (ref "J11") (pin "g35") (pinfunction "g35_g35") (pintype "bidirectional"))
      (node (ref "J11") (pin "g38") (pinfunction "g38_g38") (pintype "bidirectional"))
      (node (ref "J11") (pin "g4") (pinfunction "g4_g4") (pintype "bidirectional"))
      (node (ref "J11") (pin "g40") (pinfunction "g40_g40") (pintype "bidirectional"))
      (node (ref "J11") (pin "g5") (pinfunction "g5_g5") (pintype "bidirectional"))
      (node (ref "J11") (pin "g8") (pinfunction "g8_g8") (pintype "bidirectional"))
      (node (ref "J11") (pin "h12") (pinfunction "h12_h12") (pintype "bidirectional"))
      (node (ref "J11") (pin "h15") (pinfunction "h15_h15") (pintype "bidirectional"))
      (node (ref "J11") (pin "h18") (pinfunction "h18_h18") (pintype "bidirectional"))
      (node (ref "J11") (pin "h2") (pinfunction "h2_h2") (pintype "bidirectional"))
      (node (ref "J11") (pin "h21") (pinfunction "h21_h21") (pintype "bidirectional"))
      (node (ref "J11") (pin "h24") (pinfunction "h24_h24") (pintype "bidirectional"))
      (node (ref "J11") (pin "h27") (pinfunction "h27_h27") (pintype "bidirectional"))
      (node (ref "J11") (pin "h3") (pinfunction "h3_h3") (pintype "bidirectional"))
      (node (ref "J11") (pin "h30") (pinfunction "h30_h30") (pintype "bidirectional"))
      (node (ref "J11") (pin "h33") (pinfunction "h33_h33") (pintype "bidirectional"))
      (node (ref "J11") (pin "h36") (pinfunction "h36_h36") (pintype "bidirectional"))
      (node (ref "J11") (pin "h39") (pinfunction "h39_h39") (pintype "bidirectional"))
      (node (ref "J11") (pin "h6") (pinfunction "h6_h6") (pintype "bidirectional"))
      (node (ref "J11") (pin "h9") (pinfunction "h9_h9") (pintype "bidirectional"))
      (node (ref "J11") (pin "j1") (pinfunction "j1_j1") (pintype "bidirectional"))
      (node (ref "J11") (pin "j11") (pinfunction "j11_j11") (pintype "bidirectional"))
      (node (ref "J11") (pin "j14") (pinfunction "j14_j14") (pintype "bidirectional"))
      (node (ref "J11") (pin "j17") (pinfunction "j17_j17") (pintype "bidirectional"))
      (node (ref "J11") (pin "j20") (pinfunction "j20_j20") (pintype "bidirectional"))
      (node (ref "J11") (pin "j23") (pinfunction "j23_j23") (pintype "bidirectional"))
      (node (ref "J11") (pin "j26") (pinfunction "j26_j26") (pintype "bidirectional"))
      (node (ref "J11") (pin "j29") (pinfunction "j29_j29") (pintype "bidirectional"))
      (node (ref "J11") (pin "j32") (pinfunction "j32_j32") (pintype "bidirectional"))
      (node (ref "J11") (pin "j35") (pinfunction "j35_j35") (pintype "bidirectional"))
      (node (ref "J11") (pin "j38") (pinfunction "j38_j38") (pintype "bidirectional"))
      (node (ref "J11") (pin "j4") (pinfunction "j4_j4") (pintype "bidirectional"))
      (node (ref "J11") (pin "j40") (pinfunction "j40_j40") (pintype "bidirectional"))
      (node (ref "J11") (pin "j5") (pinfunction "j5_j5") (pintype "bidirectional"))
      (node (ref "J11") (pin "j8") (pinfunction "j8_j8") (pintype "bidirectional"))
      (node (ref "J11") (pin "k12") (pinfunction "k12_k12") (pintype "bidirectional"))
      (node (ref "J11") (pin "k15") (pinfunction "k15_k15") (pintype "bidirectional"))
      (node (ref "J11") (pin "k18") (pinfunction "k18_k18") (pintype "bidirectional"))
      (node (ref "J11") (pin "k2") (pinfunction "k2_k2") (pintype "bidirectional"))
      (node (ref "J11") (pin "k21") (pinfunction "k21_k21") (pintype "bidirectional"))
      (node (ref "J11") (pin "k24") (pinfunction "k24_k24") (pintype "bidirectional"))
      (node (ref "J11") (pin "k27") (pinfunction "k27_k27") (pintype "bidirectional"))
      (node (ref "J11") (pin "k3") (pinfunction "k3_k3") (pintype "bidirectional"))
      (node (ref "J11") (pin "k30") (pinfunction "k30_k30") (pintype "bidirectional"))
      (node (ref "J11") (pin "k33") (pinfunction "k33_k33") (pintype "bidirectional"))
      (node (ref "J11") (pin "k36") (pinfunction "k36_k36") (pintype "bidirectional"))
      (node (ref "J11") (pin "k39") (pinfunction "k39_k39") (pintype "bidirectional"))
      (node (ref "J11") (pin "k6") (pinfunction "k6_k6") (pintype "bidirectional"))
      (node (ref "J11") (pin "k9") (pinfunction "k9_k9") (pintype "bidirectional"))
    )
    (net (code "192") (name "P3V3") (class "Default")
      (node (ref "J11") (pin "c39") (pinfunction "c39_c39") (pintype "bidirectional"))
      (node (ref "J11") (pin "d36") (pinfunction "d36_d36") (pintype "bidirectional"))
      (node (ref "J11") (pin "d38") (pinfunction "d38_d38") (pintype "bidirectional"))
      (node (ref "J11") (pin "d40") (pinfunction "d40_d40") (pintype "bidirectional"))
      (node (ref "R119") (pin "1") (pinfunction "1_1") (pintype "passive"))
    )
    (net (code "193") (name "P12V0") (class "Default")
      (node (ref "J11") (pin "c35") (pinfunction "c35_c35") (pintype "bidirectional"))
      (node (ref "J11") (pin "c37") (pinfunction "c37_c37") (pintype "bidirectional"))
    )
    (net (code "194") (name "VADJ") (class "Default")
      (node (ref "J11") (pin "e39") (pinfunction "e39_e39") (pintype "bidirectional"))
      (node (ref "J11") (pin "f40") (pinfunction "f40_f40") (pintype "bidirectional"))
      (node (ref "J11") (pin "g39") (pinfunction "g39_g39") (pintype "bidirectional"))
      (node (ref "J11") (pin "h40") (pinfunction "h40_h40") (pintype "bidirectional"))
    )
    (net (code "195") (name "unconnected-(J11-Pada2)") (class "Default")
      (node (ref "J11") (pin "a2") (pinfunction "a2_a2") (pintype "bidirectional+no_connect"))
    )
    (net (code "196") (name "unconnected-(J11-Pada3)") (class "Default")
      (node (ref "J11") (pin "a3") (pinfunction "a3_a3") (pintype "bidirectional+no_connect"))
    )
    (net (code "197") (name "unconnected-(J11-Pada6)") (class "Default")
      (node (ref "J11") (pin "a6") (pinfunction "a6_a6") (pintype "bidirectional+no_connect"))
    )
    (net (code "198") (name "unconnected-(J11-Pada7)") (class "Default")
      (node (ref "J11") (pin "a7") (pinfunction "a7_a7") (pintype "bidirectional+no_connect"))
    )
    (net (code "199") (name "unconnected-(J11-Pada10)") (class "Default")
      (node (ref "J11") (pin "a10") (pinfunction "a10_a10") (pintype "bidirectional+no_connect"))
    )
    (net (code "200") (name "unconnected-(J11-Pada11)") (class "Default")
      (node (ref "J11") (pin "a11") (pinfunction "a11_a11") (pintype "bidirectional+no_connect"))
    )
    (net (code "201") (name "unconnected-(J11-Pada14)") (class "Default")
      (node (ref "J11") (pin "a14") (pinfunction "a14_a14") (pintype "bidirectional+no_connect"))
    )
    (net (code "202") (name "unconnected-(J11-Pada15)") (class "Default")
      (node (ref "J11") (pin "a15") (pinfunction "a15_a15") (pintype "bidirectional+no_connect"))
    )
    (net (code "203") (name "unconnected-(J11-Pada18)") (class "Default")
      (node (ref "J11") (pin "a18") (pinfunction "a18_a18") (pintype "bidirectional+no_connect"))
    )
    (net (code "204") (name "unconnected-(J11-Pada19)") (class "Default")
      (node (ref "J11") (pin "a19") (pinfunction "a19_a19") (pintype "bidirectional+no_connect"))
    )
    (net (code "205") (name "unconnected-(J11-Pada22)") (class "Default")
      (node (ref "J11") (pin "a22") (pinfunction "a22_a22") (pintype "bidirectional+no_connect"))
    )
    (net (code "206") (name "unconnected-(J11-Pada23)") (class "Default")
      (node (ref "J11") (pin "a23") (pinfunction "a23_a23") (pintype "bidirectional+no_connect"))
    )
    (net (code "207") (name "unconnected-(J11-Pada26)") (class "Default")
      (node (ref "J11") (pin "a26") (pinfunction "a26_a26") (pintype "bidirectional+no_connect"))
    )
    (net (code "208") (name "unconnected-(J11-Pada27)") (class "Default")
      (node (ref "J11") (pin "a27") (pinfunction "a27_a27") (pintype "bidirectional+no_connect"))
    )
    (net (code "209") (name "unconnected-(J11-Pada30)") (class "Default")
      (node (ref "J11") (pin "a30") (pinfunction "a30_a30") (pintype "bidirectional+no_connect"))
    )
    (net (code "210") (name "unconnected-(J11-Pada31)") (class "Default")
      (node (ref "J11") (pin "a31") (pinfunction "a31_a31") (pintype "bidirectional+no_connect"))
    )
    (net (code "211") (name "unconnected-(J11-Pada34)") (class "Default")
      (node (ref "J11") (pin "a34") (pinfunction "a34_a34") (pintype "bidirectional+no_connect"))
    )
    (net (code "212") (name "unconnected-(J11-Pada35)") (class "Default")
      (node (ref "J11") (pin "a35") (pinfunction "a35_a35") (pintype "bidirectional+no_connect"))
    )
    (net (code "213") (name "unconnected-(J11-Pada38)") (class "Default")
      (node (ref "J11") (pin "a38") (pinfunction "a38_a38") (pintype "bidirectional+no_connect"))
    )
    (net (code "214") (name "unconnected-(J11-Pada39)") (class "Default")
      (node (ref "J11") (pin "a39") (pinfunction "a39_a39") (pintype "bidirectional+no_connect"))
    )
    (net (code "215") (name "unconnected-(J11-Padb4)") (class "Default")
      (node (ref "J11") (pin "b4") (pinfunction "b4_b4") (pintype "bidirectional+no_connect"))
    )
    (net (code "216") (name "unconnected-(J11-Padb5)") (class "Default")
      (node (ref "J11") (pin "b5") (pinfunction "b5_b5") (pintype "bidirectional+no_connect"))
    )
    (net (code "217") (name "unconnected-(J11-Padb8)") (class "Default")
      (node (ref "J11") (pin "b8") (pinfunction "b8_b8") (pintype "bidirectional+no_connect"))
    )
    (net (code "218") (name "unconnected-(J11-Padb9)") (class "Default")
      (node (ref "J11") (pin "b9") (pinfunction "b9_b9") (pintype "bidirectional+no_connect"))
    )
    (net (code "219") (name "unconnected-(J11-Padb12)") (class "Default")
      (node (ref "J11") (pin "b12") (pinfunction "b12_b12") (pintype "bidirectional+no_connect"))
    )
    (net (code "220") (name "unconnected-(J11-Padb13)") (class "Default")
      (node (ref "J11") (pin "b13") (pinfunction "b13_b13") (pintype "bidirectional+no_connect"))
    )
    (net (code "221") (name "unconnected-(J11-Padb16)") (class "Default")
      (node (ref "J11") (pin "b16") (pinfunction "b16_b16") (pintype "bidirectional+no_connect"))
    )
    (net (code "222") (name "unconnected-(J11-Padb17)") (class "Default")
      (node (ref "J11") (pin "b17") (pinfunction "b17_b17") (pintype "bidirectional+no_connect"))
    )
    (net (code "223") (name "unconnected-(J11-Padb20)") (class "Default")
      (node (ref "J11") (pin "b20") (pinfunction "b20_b20") (pintype "bidirectional+no_connect"))
    )
    (net (code "224") (name "unconnected-(J11-Padb21)") (class "Default")
      (node (ref "J11") (pin "b21") (pinfunction "b21_b21") (pintype "bidirectional+no_connect"))
    )
    (net (code "225") (name "unconnected-(J11-Padb24)") (class "Default")
      (node (ref "J11") (pin "b24") (pinfunction "b24_b24") (pintype "bidirectional+no_connect"))
    )
    (net (code "226") (name "unconnected-(J11-Padb25)") (class "Default")
      (node (ref "J11") (pin "b25") (pinfunction "b25_b25") (pintype "bidirectional+no_connect"))
    )
    (net (code "227") (name "unconnected-(J11-Padb28)") (class "Default")
      (node (ref "J11") (pin "b28") (pinfunction "b28_b28") (pintype "bidirectional+no_connect"))
    )
    (net (code "228") (name "unconnected-(J11-Padb29)") (class "Default")
      (node (ref "J11") (pin "b29") (pinfunction "b29_b29") (pintype "bidirectional+no_connect"))
    )
    (net (code "229") (name "unconnected-(J11-Padb32)") (class "Default")
      (node (ref "J11") (pin "b32") (pinfunction "b32_b32") (pintype "bidirectional+no_connect"))
    )
    (net (code "230") (name "unconnected-(J11-Padb33)") (class "Default")
      (node (ref "J11") (pin "b33") (pinfunction "b33_b33") (pintype "bidirectional+no_connect"))
    )
    (net (code "231") (name "unconnected-(J11-Padb36)") (class "Default")
      (node (ref "J11") (pin "b36") (pinfunction "b36_b36") (pintype "bidirectional+no_connect"))
    )
    (net (code "232") (name "unconnected-(J11-Padb37)") (class "Default")
      (node (ref "J11") (pin "b37") (pinfunction "b37_b37") (pintype "bidirectional+no_connect"))
    )
    (net (code "233") (name "unconnected-(J11-Padb40)") (class "Default")
      (node (ref "J11") (pin "b40") (pinfunction "b40_b40") (pintype "bidirectional+no_connect"))
    )
    (net (code "234") (name "unconnected-(J11-Padc2)") (class "Default")
      (node (ref "J11") (pin "c2") (pinfunction "c2_c2") (pintype "bidirectional+no_connect"))
    )
    (net (code "235") (name "unconnected-(J11-Padc3)") (class "Default")
      (node (ref "J11") (pin "c3") (pinfunction "c3_c3") (pintype "bidirectional+no_connect"))
    )
    (net (code "236") (name "unconnected-(J11-Padc6)") (class "Default")
      (node (ref "J11") (pin "c6") (pinfunction "c6_c6") (pintype "bidirectional+no_connect"))
    )
    (net (code "237") (name "unconnected-(J11-Padc7)") (class "Default")
      (node (ref "J11") (pin "c7") (pinfunction "c7_c7") (pintype "bidirectional+no_connect"))
    )
    (net (code "238") (name "unconnected-(J11-Padd1)") (class "Default")
      (node (ref "J11") (pin "d1") (pinfunction "d1_d1") (pintype "bidirectional+no_connect"))
    )
    (net (code "239") (name "unconnected-(J11-Padd4)") (class "Default")
      (node (ref "J11") (pin "d4") (pinfunction "d4_d4") (pintype "bidirectional+no_connect"))
    )
    (net (code "240") (name "unconnected-(J11-Padd5)") (class "Default")
      (node (ref "J11") (pin "d5") (pinfunction "d5_d5") (pintype "bidirectional+no_connect"))
    )
    (net (code "241") (name "unconnected-(J11-Padd29)") (class "Default")
      (node (ref "J11") (pin "d29") (pinfunction "d29_d29") (pintype "bidirectional+no_connect"))
    )
    (net (code "242") (name "unconnected-(J11-Padd33)") (class "Default")
      (node (ref "J11") (pin "d33") (pinfunction "d33_d33") (pintype "bidirectional+no_connect"))
    )
    (net (code "243") (name "unconnected-(J11-Padd34)") (class "Default")
      (node (ref "J11") (pin "d34") (pinfunction "d34_d34") (pintype "bidirectional+no_connect"))
    )
    (net (code "244") (name "unconnected-(J11-Padj39)") (class "Default")
      (node (ref "J11") (pin "j39") (pinfunction "j39_j39") (pintype "bidirectional"))
    )
    (net (code "245") (name "unconnected-(J11-Padk1)") (class "Default")
      (node (ref "J11") (pin "k1") (pinfunction "k1_k1") (pintype "bidirectional+no_connect"))
    )
  )
)
